# 6coils.net
KiCad netlist of a schematic drawn in EasyEDA
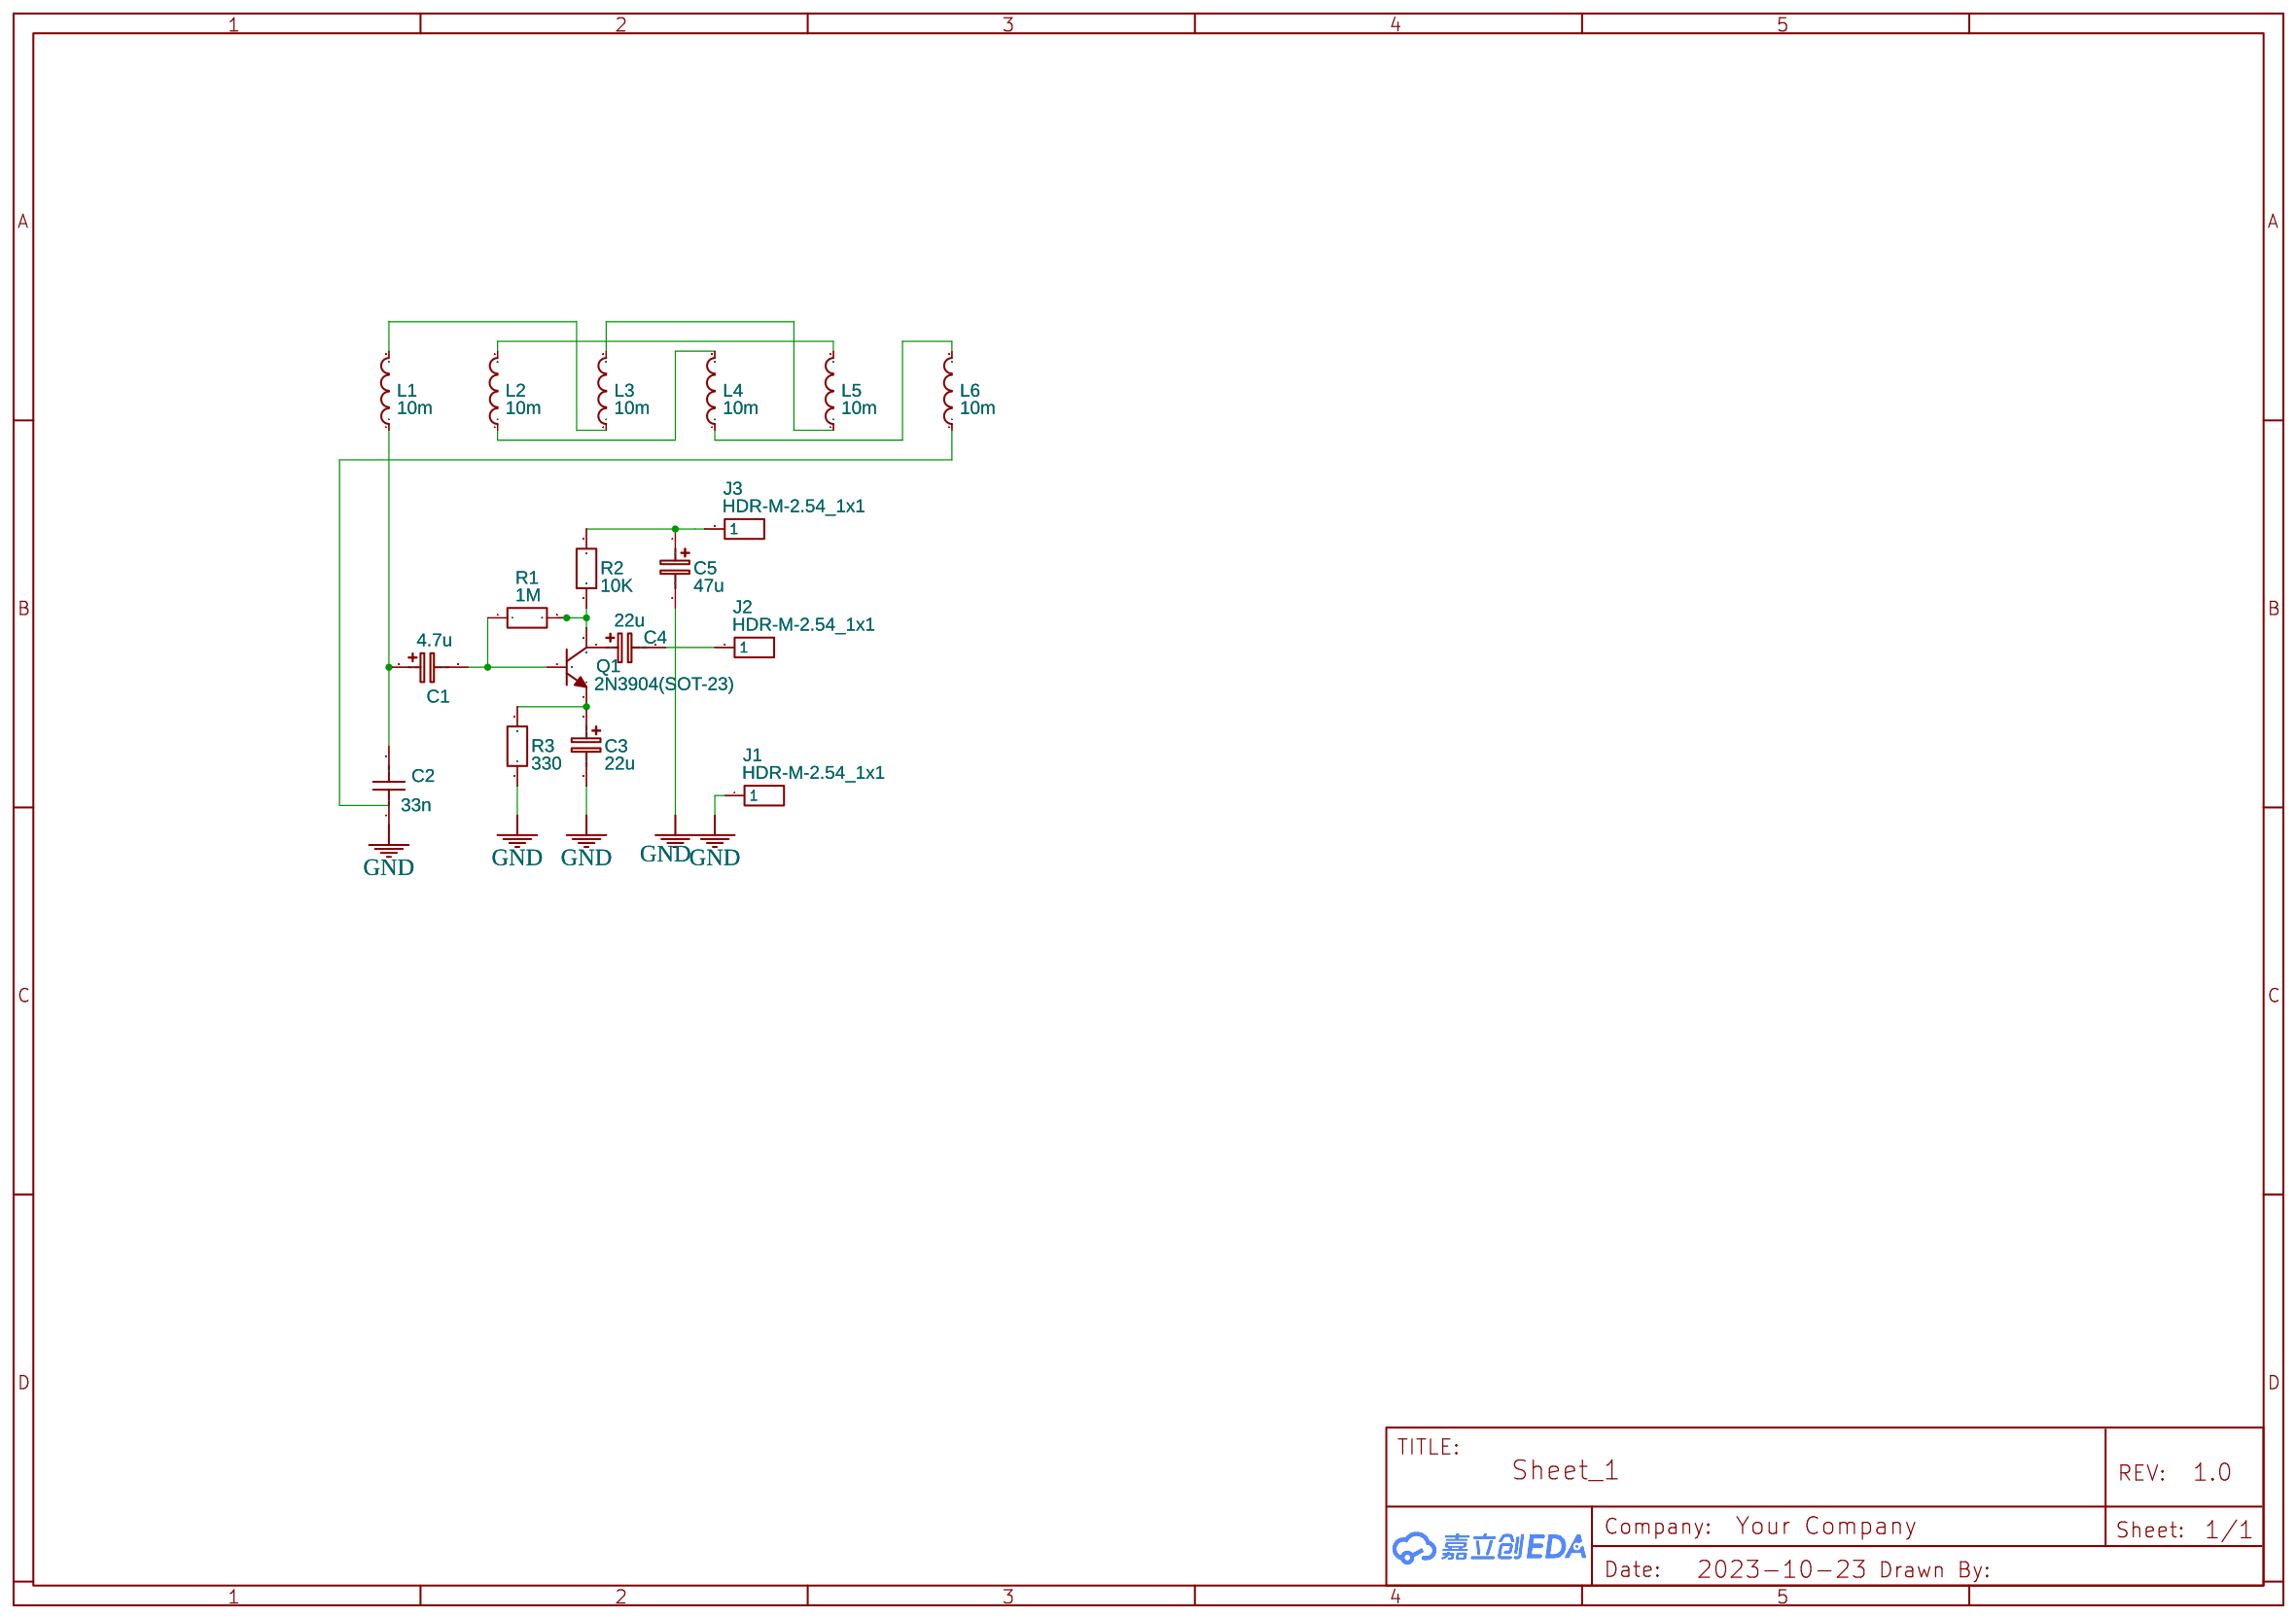
[diagram p0: schematic sheet]

(export (version "E")
  (design (tool "Eeschema 10.0.6"))
  (components
    (comp (ref "C1") (value "4.7u") (libsource (lib "") (part "C_Tan_SMD_A_EU")))
    (comp (ref "C2") (value "33n") (libsource (lib "") (part "C_0603_US")))
    (comp (ref "C3") (value "22u") (libsource (lib "") (part "C_Tan_SMD_A_EU_2")))
    (comp (ref "C4") (value "22u") (libsource (lib "") (part "C_Tan_SMD_A_EU_3")))
    (comp (ref "C5") (value "47u") (libsource (lib "") (part "C_Tan_SMD_A_EU_1")))
    (comp (ref "J1")
      (value "HDR-M-2.54_1x1")
      (fields (field (name "BOM_Supplier Part") "C81276"))
      (libsource (lib "") (part "HDR-M-2.54_1x1"))
    )
    (comp (ref "J2")
      (value "HDR-M-2.54_1x1")
      (fields (field (name "BOM_Supplier Part") "C81276"))
      (libsource (lib "") (part "HDR-M-2.54_1x1"))
    )
    (comp (ref "J3")
      (value "HDR-M-2.54_1x1")
      (fields (field (name "BOM_Supplier Part") "C81276"))
      (libsource (lib "") (part "HDR-M-2.54_1x1"))
    )
    (comp (ref "L1") (value "10m") (libsource (lib "") (part "L0603_US")))
    (comp (ref "L2") (value "10m") (libsource (lib "") (part "L0603_US")))
    (comp (ref "L3") (value "10m") (libsource (lib "") (part "L0603_US")))
    (comp (ref "L4") (value "10m") (libsource (lib "") (part "L0603_US")))
    (comp (ref "L5") (value "10m") (libsource (lib "") (part "L0603_US")))
    (comp (ref "L6") (value "10m") (libsource (lib "") (part "L0603_US")))
    (comp (ref "Q1")
      (value "2N3904(SOT-23)")
      (fields
        (field (name "BOM_Manufacturer Part") "2n3904S-RTK/PS")
        (field (name "BOM_Supplier Part") "C18536")
      )
      (libsource (lib "") (part "2N3904(SOT-23)"))
    )
    (comp (ref "R1") (value "1M") (libsource (lib "") (part "R_0603_EU")))
    (comp (ref "R2") (value "10K") (libsource (lib "") (part "R_0603_EU_1")))
    (comp (ref "R3") (value "330") (libsource (lib "") (part "R_0603_EU_1")))
  )
  (nets
    (net (code "1") (name "GND") (class "Default")
      (node (ref "C2") (pin "1") (pinfunction "1_1") (pintype "unspecified"))
      (node (ref "C3") (pin "2") (pinfunction "2_2") (pintype "unspecified"))
      (node (ref "C5") (pin "2") (pinfunction "2_2") (pintype "unspecified"))
      (node (ref "J1") (pin "1") (pinfunction "1_1") (pintype "input"))
      (node (ref "R3") (pin "1") (pinfunction "1_1") (pintype "unspecified"))
    )
    (net (code "2") (name "Net-(C1-Pad1)") (class "Default")
      (node (ref "C1") (pin "1") (pinfunction "1_1") (pintype "unspecified"))
      (node (ref "C2") (pin "2") (pinfunction "2_2") (pintype "unspecified"))
      (node (ref "L1") (pin "1") (pinfunction "1_1") (pintype "unspecified"))
    )
    (net (code "3") (name "Net-(C4-Pad2)") (class "Default")
      (node (ref "C4") (pin "2") (pinfunction "2_2") (pintype "unspecified"))
      (node (ref "J2") (pin "1") (pinfunction "1_1") (pintype "input"))
    )
    (net (code "4") (name "Net-(C5-Pad1)") (class "Default")
      (node (ref "C5") (pin "1") (pinfunction "1_1") (pintype "unspecified"))
      (node (ref "J3") (pin "1") (pinfunction "1_1") (pintype "input"))
      (node (ref "R2") (pin "2") (pinfunction "2_2") (pintype "unspecified"))
    )
    (net (code "5") (name "Net-(L1-Pad2)") (class "Default")
      (node (ref "L1") (pin "2") (pinfunction "2_2") (pintype "unspecified"))
      (node (ref "L3") (pin "1") (pinfunction "1_1") (pintype "unspecified"))
    )
    (net (code "6") (name "Net-(L2-Pad1)") (class "Default")
      (node (ref "L2") (pin "1") (pinfunction "1_1") (pintype "unspecified"))
      (node (ref "L4") (pin "2") (pinfunction "2_2") (pintype "unspecified"))
    )
    (net (code "7") (name "Net-(L2-Pad2)") (class "Default")
      (node (ref "L2") (pin "2") (pinfunction "2_2") (pintype "unspecified"))
      (node (ref "L5") (pin "2") (pinfunction "2_2") (pintype "unspecified"))
    )
    (net (code "8") (name "Net-(L3-Pad2)") (class "Default")
      (node (ref "L3") (pin "2") (pinfunction "2_2") (pintype "unspecified"))
      (node (ref "L5") (pin "1") (pinfunction "1_1") (pintype "unspecified"))
    )
    (net (code "9") (name "Net-(L4-Pad1)") (class "Default")
      (node (ref "L4") (pin "1") (pinfunction "1_1") (pintype "unspecified"))
      (node (ref "L6") (pin "2") (pinfunction "2_2") (pintype "unspecified"))
    )
    (net (code "10") (name "Net-(Q1-B)") (class "Default")
      (node (ref "C1") (pin "2") (pinfunction "2_2") (pintype "unspecified"))
      (node (ref "Q1") (pin "2") (pinfunction "B_2") (pintype "input"))
      (node (ref "R1") (pin "1") (pinfunction "1_1") (pintype "unspecified"))
    )
    (net (code "11") (name "Net-(Q1-C)") (class "Default")
      (node (ref "Q1") (pin "3") (pinfunction "C_3") (pintype "input"))
      (node (ref "R1") (pin "2") (pinfunction "2_2") (pintype "unspecified"))
      (node (ref "R2") (pin "1") (pinfunction "1_1") (pintype "unspecified"))
    )
    (net (code "12") (name "Net-(Q1-E)") (class "Default")
      (node (ref "C3") (pin "1") (pinfunction "1_1") (pintype "unspecified"))
      (node (ref "Q1") (pin "1") (pinfunction "E_1") (pintype "input"))
      (node (ref "R3") (pin "2") (pinfunction "2_2") (pintype "unspecified"))
    )
    (net (code "13") (name "unconnected-(C4-Pad1)") (class "Default")
      (node (ref "C4") (pin "1") (pinfunction "1_1") (pintype "unspecified"))
    )
    (net (code "14") (name "unconnected-(L6-Pad1)") (class "Default")
      (node (ref "L6") (pin "1") (pinfunction "1_1") (pintype "unspecified"))
    )
  )
)
